# NTC_Thermistor_100K_VDiv.net
KiCad netlist of a schematic drawn in Altium Designer
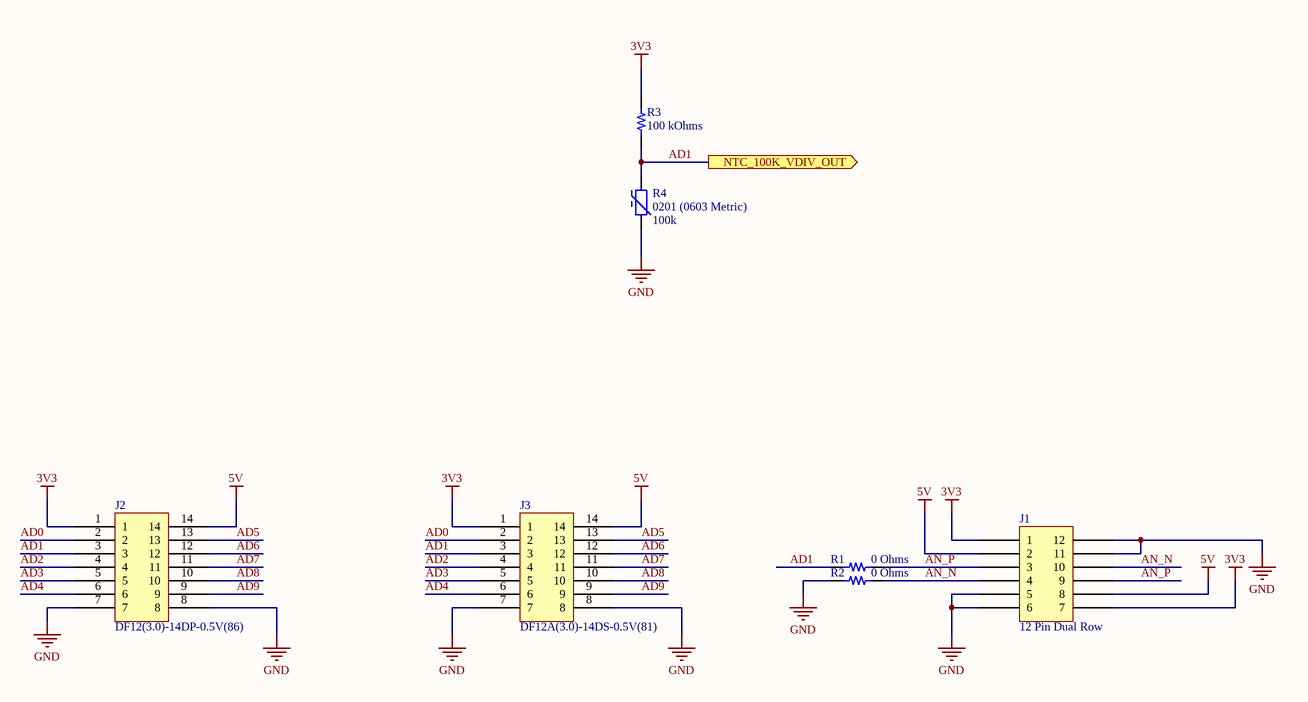
[diagram p0: NTC Thermistor 100K VDiv.SchDoc]

(export (version "E")
  (design (tool "Eeschema 10.0.6"))
  (components
    (comp (ref "J1")
      (value "12 Pin Dual Row")
      (footprint "TE 5650118-3 Card Edge")
      (libsource (lib "CelestialUseful") (part "12 Pin Dual Row"))
    )
    (comp (ref "J2")
      (value "DF12(3.0)-14DP-0.5V(86)")
      (footprint "HIROSE DF12 3.0-14DP-0.5V 86")
      (description "CONN HDR 14POS SMD GOLD")
      (fields (field (name "MANUFACTURER") "Hirose Electric Co Ltd"))
      (libsource (lib "altiumlibrary.com") (part "14 Pin Dual Row"))
    )
    (comp (ref "J3")
      (value "DF12A(3.0)-14DS-0.5V(81)")
      (footprint "HIROSE DF12A 3.0-14DS-0.5V 81")
      (description "CONN RCPT 14POS SMD GOLD")
      (fields (field (name "MANUFACTURER") "Hirose Electric Co Ltd"))
      (libsource (lib "altiumlibrary.com") (part "14 Pin Dual Row"))
    )
    (comp (ref "R1")
      (value "0 Ohms")
      (footprint "RES 0603_1608")
      (description "RES SMD 0 OHM JUMPER 1/10W 0603")
      (fields
        (field (name "PART NUMBER") "ERJ-3GEY0R00V")
        (field (name "MANUFACTURER") "Panasonic Electronic Components")
      )
      (libsource (lib "altiumlibrary.com") (part "Resistor"))
    )
    (comp (ref "R2")
      (value "0 Ohms")
      (footprint "RES 0603_1608")
      (description "RES SMD 0 OHM JUMPER 1/10W 0603")
      (fields
        (field (name "PART NUMBER") "ERJ-3GEY0R00V")
        (field (name "MANUFACTURER") "Panasonic Electronic Components")
      )
      (libsource (lib "altiumlibrary.com") (part "Resistor"))
    )
    (comp (ref "R3")
      (value "100 kOhms")
      (footprint "RES 0603_1608")
      (description "RES SMD 100K OHM 1% 1/10W 0603")
      (fields
        (field (name "PART NUMBER") "ERJ-3EKF1003V")
        (field (name "MANUFACTURER") "Panasonic Electronic Components")
      )
      (libsource (lib "altiumlibrary.com") (part "Resistor"))
    )
    (comp (ref "R4")
      (value "NCP03WF104F05RL")
      (footprint "NTC 0201_0603")
      (description "THERM NTC 100KOHM 4250K 0201")
      (fields
        (field (name "MANUFACTURER") "Murata Electronics")
        (field (name "PACKAGE / CASE") "0201 (0603 Metric)")
        (field (name "RESISTANCE IN OHMS @ 25°C") "100k")
      )
      (libsource (lib "altiumlibrary.com") (part "Thermistor"))
    )
  )
  (nets
    (net (code "1") (name "/AD0") (class "Default")
      (node (ref "J2") (pin "2") (pinfunction "2_2") (pintype "passive"))
      (node (ref "J3") (pin "2") (pinfunction "2_2") (pintype "passive"))
    )
    (net (code "2") (name "/AD1") (class "Default")
      (node (ref "J2") (pin "3") (pinfunction "3_3") (pintype "passive"))
      (node (ref "J3") (pin "3") (pinfunction "3_3") (pintype "passive"))
      (node (ref "R1") (pin "1") (pinfunction "1_1") (pintype "passive"))
      (node (ref "R3") (pin "1") (pinfunction "1_1") (pintype "passive"))
      (node (ref "R4") (pin "1") (pinfunction "1_1") (pintype "passive"))
    )
    (net (code "3") (name "/AD2") (class "Default")
      (node (ref "J2") (pin "4") (pinfunction "4_4") (pintype "passive"))
      (node (ref "J3") (pin "4") (pinfunction "4_4") (pintype "passive"))
    )
    (net (code "4") (name "/AD3") (class "Default")
      (node (ref "J2") (pin "5") (pinfunction "5_5") (pintype "passive"))
      (node (ref "J3") (pin "5") (pinfunction "5_5") (pintype "passive"))
    )
    (net (code "5") (name "/AD4") (class "Default")
      (node (ref "J2") (pin "6") (pinfunction "6_6") (pintype "passive"))
      (node (ref "J3") (pin "6") (pinfunction "6_6") (pintype "passive"))
    )
    (net (code "6") (name "/AD5") (class "Default")
      (node (ref "J2") (pin "13") (pinfunction "13_13") (pintype "passive"))
      (node (ref "J3") (pin "13") (pinfunction "13_13") (pintype "passive"))
    )
    (net (code "7") (name "/AD6") (class "Default")
      (node (ref "J2") (pin "12") (pinfunction "12_12") (pintype "passive"))
      (node (ref "J3") (pin "12") (pinfunction "12_12") (pintype "passive"))
    )
    (net (code "8") (name "/AD7") (class "Default")
      (node (ref "J2") (pin "11") (pinfunction "11_11") (pintype "passive"))
      (node (ref "J3") (pin "11") (pinfunction "11_11") (pintype "passive"))
    )
    (net (code "9") (name "/AD8") (class "Default")
      (node (ref "J2") (pin "10") (pinfunction "10_10") (pintype "passive"))
      (node (ref "J3") (pin "10") (pinfunction "10_10") (pintype "passive"))
    )
    (net (code "10") (name "/AD9") (class "Default")
      (node (ref "J2") (pin "9") (pinfunction "9_9") (pintype "passive"))
      (node (ref "J3") (pin "9") (pinfunction "9_9") (pintype "passive"))
    )
    (net (code "11") (name "/AN_N") (class "Default")
      (node (ref "J1") (pin "10") (pinfunction "10_10") (pintype "passive"))
      (node (ref "J1") (pin "4") (pinfunction "4_4") (pintype "passive"))
      (node (ref "R2") (pin "2") (pinfunction "2_2") (pintype "passive"))
    )
    (net (code "12") (name "/AN_P") (class "Default")
      (node (ref "J1") (pin "3") (pinfunction "3_3") (pintype "passive"))
      (node (ref "J1") (pin "9") (pinfunction "9_9") (pintype "passive"))
      (node (ref "R1") (pin "2") (pinfunction "2_2") (pintype "passive"))
    )
    (net (code "13") (name "3V3") (class "Default")
      (node (ref "J1") (pin "1") (pinfunction "1_1") (pintype "passive"))
      (node (ref "J1") (pin "7") (pinfunction "7_7") (pintype "passive"))
      (node (ref "J2") (pin "1") (pinfunction "1_1") (pintype "passive"))
      (node (ref "J3") (pin "1") (pinfunction "1_1") (pintype "passive"))
      (node (ref "R3") (pin "2") (pinfunction "2_2") (pintype "passive"))
    )
    (net (code "14") (name "5V") (class "Default")
      (node (ref "J1") (pin "2") (pinfunction "2_2") (pintype "passive"))
      (node (ref "J1") (pin "8") (pinfunction "8_8") (pintype "passive"))
      (node (ref "J2") (pin "14") (pinfunction "14_14") (pintype "passive"))
      (node (ref "J3") (pin "14") (pinfunction "14_14") (pintype "passive"))
    )
    (net (code "15") (name "GND") (class "Default")
      (node (ref "J1") (pin "11") (pinfunction "11_11") (pintype "passive"))
      (node (ref "J1") (pin "12") (pinfunction "12_12") (pintype "passive"))
      (node (ref "J1") (pin "5") (pinfunction "5_5") (pintype "passive"))
      (node (ref "J1") (pin "6") (pinfunction "6_6") (pintype "passive"))
      (node (ref "J2") (pin "7") (pinfunction "7_7") (pintype "passive"))
      (node (ref "J2") (pin "8") (pinfunction "8_8") (pintype "passive"))
      (node (ref "J3") (pin "7") (pinfunction "7_7") (pintype "passive"))
      (node (ref "J3") (pin "8") (pinfunction "8_8") (pintype "passive"))
      (node (ref "R2") (pin "1") (pinfunction "1_1") (pintype "passive"))
      (node (ref "R4") (pin "2") (pinfunction "2_2") (pintype "passive"))
    )
  )
)
